# applicant_skillchk.net
KiCad netlist of a schematic drawn in EAGLE
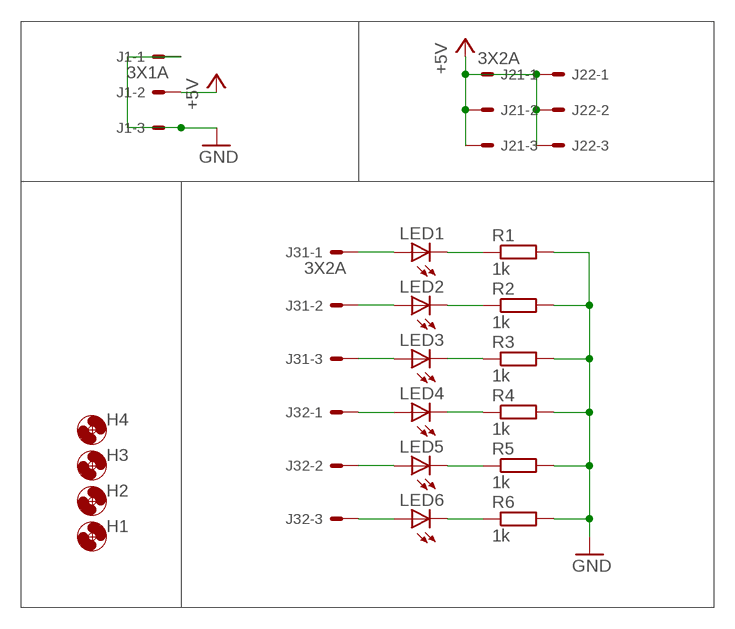
[diagram p0: schematic, sheet 1]

(export (version "E")
  (design (tool "Eeschema 10.0.6"))
  (components
    (comp (ref "H1")
      (value "HOLE3.3M3BOLT")
      (footprint "eagle-import:HOLE3.3")
      (libsource (lib "eagle-import") (part "HOLE3.3M3BOLT"))
    )
    (comp (ref "H2")
      (value "HOLE3.3M3BOLT")
      (footprint "eagle-import:HOLE3.3")
      (libsource (lib "eagle-import") (part "HOLE3.3M3BOLT"))
    )
    (comp (ref "H3")
      (value "HOLE3.3M3BOLT")
      (footprint "eagle-import:HOLE3.3")
      (libsource (lib "eagle-import") (part "HOLE3.3M3BOLT"))
    )
    (comp (ref "H4")
      (value "HOLE3.3M3BOLT")
      (footprint "eagle-import:HOLE3.3")
      (libsource (lib "eagle-import") (part "HOLE3.3M3BOLT"))
    )
    (comp (ref "J1")
      (value "3X1A")
      (footprint "eagle-import:37203-62A3-003")
      (libsource (lib "eagle-import") (part "3X1A"))
    )
    (comp (ref "J2")
      (value "3X2A")
      (footprint "eagle-import:37206-62A3-003")
      (libsource (lib "eagle-import") (part "3X2A"))
    )
    (comp (ref "J3")
      (value "3X2A")
      (footprint "eagle-import:37206-62A3-003")
      (libsource (lib "eagle-import") (part "3X2A"))
    )
    (comp (ref "LED1")
      (value "LED5MM")
      (footprint "eagle-import:LED5MM")
      (libsource (lib "eagle-import") (part "LED5MM"))
    )
    (comp (ref "LED2")
      (value "LED5MM")
      (footprint "eagle-import:LED5MM")
      (libsource (lib "eagle-import") (part "LED5MM"))
    )
    (comp (ref "LED3")
      (value "LED5MM")
      (footprint "eagle-import:LED5MM")
      (libsource (lib "eagle-import") (part "LED5MM"))
    )
    (comp (ref "LED4")
      (value "LED5MM")
      (footprint "eagle-import:LED5MM")
      (libsource (lib "eagle-import") (part "LED5MM"))
    )
    (comp (ref "LED5")
      (value "LED5MM")
      (footprint "eagle-import:LED5MM")
      (libsource (lib "eagle-import") (part "LED5MM"))
    )
    (comp (ref "LED6")
      (value "LED5MM")
      (footprint "eagle-import:LED5MM")
      (libsource (lib "eagle-import") (part "LED5MM"))
    )
    (comp (ref "R1")
      (value "1k")
      (footprint "eagle-import:R3216W")
      (libsource (lib "eagle-import") (part "R-EU_R3216W"))
    )
    (comp (ref "R2")
      (value "1k")
      (footprint "eagle-import:R3216W")
      (libsource (lib "eagle-import") (part "R-EU_R3216W"))
    )
    (comp (ref "R3")
      (value "1k")
      (footprint "eagle-import:R3216W")
      (libsource (lib "eagle-import") (part "R-EU_R3216W"))
    )
    (comp (ref "R4")
      (value "1k")
      (footprint "eagle-import:R3216W")
      (libsource (lib "eagle-import") (part "R-EU_R3216W"))
    )
    (comp (ref "R5")
      (value "1k")
      (footprint "eagle-import:R3216W")
      (libsource (lib "eagle-import") (part "R-EU_R3216W"))
    )
    (comp (ref "R6")
      (value "1k")
      (footprint "eagle-import:R3216W")
      (libsource (lib "eagle-import") (part "R-EU_R3216W"))
    )
  )
  (nets
    (net (code "1") (name "+5V") (class "Default")
      (node (ref "J1") (pin "1-2") (pinfunction "S_1-2") (pintype "passive"))
      (node (ref "J2") (pin "1-1") (pinfunction "S_1-1") (pintype "passive"))
      (node (ref "J2") (pin "1-2") (pinfunction "S_1-2") (pintype "passive"))
      (node (ref "J2") (pin "1-3") (pinfunction "S_1-3") (pintype "passive"))
      (node (ref "J2") (pin "2-1") (pinfunction "S_2-1") (pintype "passive"))
      (node (ref "J2") (pin "2-2") (pinfunction "S_2-2") (pintype "passive"))
      (node (ref "J2") (pin "2-3") (pinfunction "S_2-3") (pintype "passive"))
    )
    (net (code "2") (name "GND") (class "Default")
      (node (ref "J1") (pin "1-1") (pinfunction "S_1-1") (pintype "passive"))
      (node (ref "J1") (pin "1-3") (pinfunction "S_1-3") (pintype "passive"))
      (node (ref "R1") (pin "2") (pinfunction "2_2") (pintype "passive"))
      (node (ref "R2") (pin "2") (pinfunction "2_2") (pintype "passive"))
      (node (ref "R3") (pin "2") (pinfunction "2_2") (pintype "passive"))
      (node (ref "R4") (pin "2") (pinfunction "2_2") (pintype "passive"))
      (node (ref "R5") (pin "2") (pinfunction "2_2") (pintype "passive"))
      (node (ref "R6") (pin "2") (pinfunction "2_2") (pintype "passive"))
    )
    (net (code "3") (name "Net-(J3A-S)") (class "Default")
      (node (ref "J3") (pin "1-1") (pinfunction "S_1-1") (pintype "passive"))
      (node (ref "LED1") (pin "A") (pinfunction "A_A") (pintype "passive"))
    )
    (net (code "4") (name "Net-(J3B-S)") (class "Default")
      (node (ref "J3") (pin "1-2") (pinfunction "S_1-2") (pintype "passive"))
      (node (ref "LED2") (pin "A") (pinfunction "A_A") (pintype "passive"))
    )
    (net (code "5") (name "Net-(J3C-S)") (class "Default")
      (node (ref "J3") (pin "1-3") (pinfunction "S_1-3") (pintype "passive"))
      (node (ref "LED3") (pin "A") (pinfunction "A_A") (pintype "passive"))
    )
    (net (code "6") (name "Net-(J3D-S)") (class "Default")
      (node (ref "J3") (pin "2-1") (pinfunction "S_2-1") (pintype "passive"))
      (node (ref "LED4") (pin "A") (pinfunction "A_A") (pintype "passive"))
    )
    (net (code "7") (name "Net-(J3E-S)") (class "Default")
      (node (ref "J3") (pin "2-2") (pinfunction "S_2-2") (pintype "passive"))
      (node (ref "LED5") (pin "A") (pinfunction "A_A") (pintype "passive"))
    )
    (net (code "8") (name "Net-(J3F-S)") (class "Default")
      (node (ref "J3") (pin "2-3") (pinfunction "S_2-3") (pintype "passive"))
      (node (ref "LED6") (pin "A") (pinfunction "A_A") (pintype "passive"))
    )
    (net (code "9") (name "Net-(LED1-C)") (class "Default")
      (node (ref "LED1") (pin "K") (pinfunction "C_K") (pintype "passive"))
      (node (ref "R1") (pin "1") (pinfunction "1_1") (pintype "passive"))
    )
    (net (code "10") (name "Net-(LED2-C)") (class "Default")
      (node (ref "LED2") (pin "K") (pinfunction "C_K") (pintype "passive"))
      (node (ref "R2") (pin "1") (pinfunction "1_1") (pintype "passive"))
    )
    (net (code "11") (name "Net-(LED3-C)") (class "Default")
      (node (ref "LED3") (pin "K") (pinfunction "C_K") (pintype "passive"))
      (node (ref "R3") (pin "1") (pinfunction "1_1") (pintype "passive"))
    )
    (net (code "12") (name "Net-(LED4-C)") (class "Default")
      (node (ref "LED4") (pin "K") (pinfunction "C_K") (pintype "passive"))
      (node (ref "R4") (pin "1") (pinfunction "1_1") (pintype "passive"))
    )
    (net (code "13") (name "Net-(LED5-C)") (class "Default")
      (node (ref "LED5") (pin "K") (pinfunction "C_K") (pintype "passive"))
      (node (ref "R5") (pin "1") (pinfunction "1_1") (pintype "passive"))
    )
    (net (code "14") (name "Net-(LED6-C)") (class "Default")
      (node (ref "LED6") (pin "K") (pinfunction "C_K") (pintype "passive"))
      (node (ref "R6") (pin "1") (pinfunction "1_1") (pintype "passive"))
    )
  )
)
